# 06_Power.net
KiCad netlist of a schematic drawn in Altium Designer
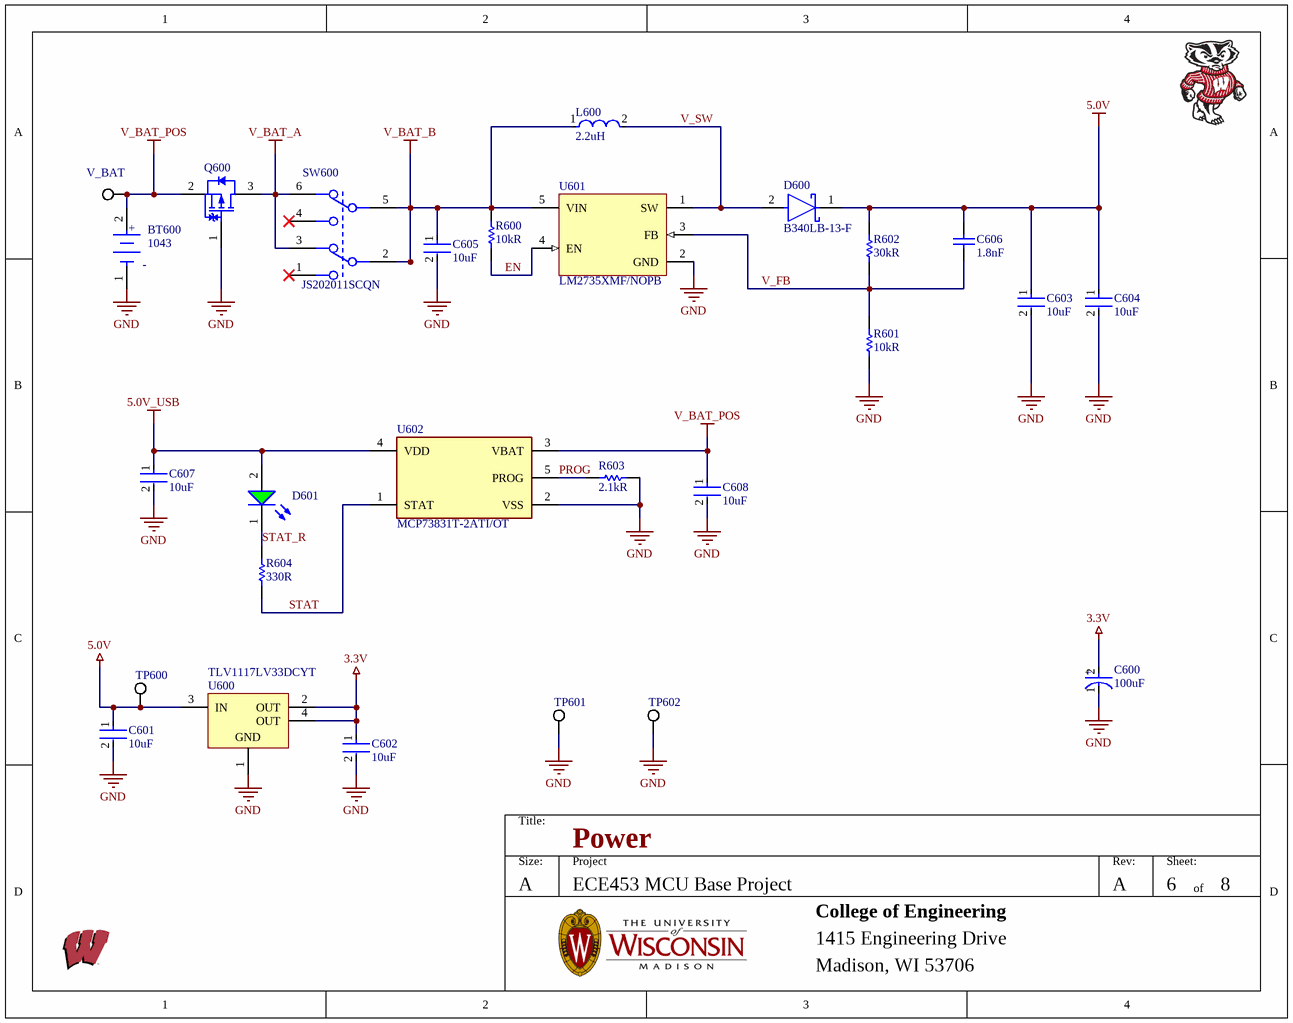
[diagram p0: 06_Power.SchDoc]

(export (version "E")
  (design (tool "Eeschema 10.0.6"))
  (components
    (comp (ref "BT600")
      (value "1043")
      (footprint "BAT_1043")
      (description "Conn Terminal Strip 2 POS Solder Lug ST")
      (fields
        (field (name "MANUFACTURER") "Keystone Electronics")
        (field (name "MANUFACTURER PART NUMBER 1") "1043")
      )
      (libsource (lib "ECE453_S24") (part "1043"))
    )
    (comp (ref "C600")
      (value "100uF")
      (footprint "FP-SD8-MFG")
      (description "CAP ALUM 100UF 20% 25V SMD")
      (fields (field (name "VOLTAGE") "25V") (field (name "TOLERANCE") "20%"))
      (libsource (lib "Altium Content Vault") (part "a00bbbee19879c290e62620ae7e47b1"))
    )
    (comp (ref "C601")
      (value "10uF")
      (footprint "FP-C0805C-DG-MFG")
      (description "CAP CER 10UF 10V X5R 0805")
      (fields (field (name "TOLERANCE") "10%") (field (name "MANUFACTURER PART NUMBER") "C0805C106K8PACTU"))
      (libsource (lib "Altium Content Vault") (part "11868f565c42a9108669ba33697ecf6"))
    )
    (comp (ref "C602")
      (value "10uF")
      (footprint "FP-C0805C-DG-MFG")
      (description "CAP CER 10UF 10V X5R 0805")
      (fields (field (name "TOLERANCE") "10%") (field (name "MANUFACTURER PART NUMBER") "C0805C106K8PACTU"))
      (libsource (lib "Altium Content Vault") (part "11868f565c42a9108669ba33697ecf6"))
    )
    (comp (ref "C603")
      (value "10uF")
      (footprint "FP-C0805C-DG-MFG")
      (description "CAP CER 10UF 10V X5R 0805")
      (fields (field (name "TOLERANCE") "10%") (field (name "MANUFACTURER PART NUMBER") "C0805C106K8PACTU"))
      (libsource (lib "Altium Content Vault") (part "11868f565c42a9108669ba33697ecf6"))
    )
    (comp (ref "C604")
      (value "10uF")
      (footprint "FP-C0805C-DG-MFG")
      (description "CAP CER 10UF 10V X5R 0805")
      (fields (field (name "TOLERANCE") "10%") (field (name "MANUFACTURER PART NUMBER") "C0805C106K8PACTU"))
      (libsource (lib "Altium Content Vault") (part "11868f565c42a9108669ba33697ecf6"))
    )
    (comp (ref "C605")
      (value "10uF")
      (footprint "FP-C0805C-DG-MFG")
      (description "CAP CER 10UF 10V X5R 0805")
      (fields (field (name "TOLERANCE") "10%") (field (name "MANUFACTURER PART NUMBER") "C0805C106K8PACTU"))
      (libsource (lib "Altium Content Vault") (part "11868f565c42a9108669ba33697ecf6"))
    )
    (comp (ref "C606")
      (value "1.8nF")
      (footprint "CAPC2013X70X45LL10T25")
      (fields (field (name "PART NUMBER") "GRM2165C1H182JA01D") (field (name "MANUFACTURER") "Murata"))
      (libsource (lib "Altium Content Vault") (part "CAP"))
    )
    (comp (ref "C607")
      (value "10uF")
      (footprint "FP-C0805C-DG-MFG")
      (description "CAP CER 10UF 10V X5R 0805")
      (fields (field (name "TOLERANCE") "10%") (field (name "MANUFACTURER PART NUMBER") "C0805C106K8PACTU"))
      (libsource (lib "Altium Content Vault") (part "11868f565c42a9108669ba33697ecf6"))
    )
    (comp (ref "C608")
      (value "10uF")
      (footprint "FP-C0805C-DG-MFG")
      (description "CAP CER 10UF 10V X5R 0805")
      (fields (field (name "TOLERANCE") "10%") (field (name "MANUFACTURER PART NUMBER") "C0805C106K8PACTU"))
      (libsource (lib "Altium Content Vault") (part "11868f565c42a9108669ba33697ecf6"))
    )
    (comp (ref "D600")
      (value "B340LB-13-F")
      (footprint "FP-SMB-MFG")
      (description "DIODE SCHOTTKY 40V 3A SMB")
      (fields
        (field (name "OCTOPART") "https://octopart.com/b340lb-13-f-diodes+inc.-325823")
        (field (name "MANUFACTURER") "Diodes Inc.")
      )
      (libsource (lib "Altium Content Vault") (part "1d6ec82d83fb6aee721767c19dac4b9"))
    )
    (comp (ref "D601")
      (value "~")
      (footprint "WL-SMCW_0805_150080xx75000")
      (libsource (lib "Altium Content Vault") (part "LED_Green_2A-1K"))
    )
    (comp (ref "L600")
      (value "2.2uH")
      (footprint "FP-NR4018-MFG")
      (description "SMD Power Inductors 2.2uH ±20% 2.2A 50.4mΩ")
      (fields (field (name "TOLERANCE") "20%"))
      (libsource (lib "Altium Content Vault") (part "725321dda6339637d4d059423bc1c3c"))
    )
    (comp (ref "Q600")
      (value "~")
      (footprint "TOSH-SOT-23F_V")
      (fields (field (name "MANUFACTURER") "Toshiba"))
      (libsource (lib "Altium Content Vault") (part "PEMOS-GSD-3_C"))
    )
    (comp (ref "R600")
      (value "10kR")
      (footprint "RESC2013X60X35NL10T20")
      (description "Chip Resistor, 10 KOhm, +/- 1%, 0.125 W, -55 to 155 degC, 0805 (2012 Metric), RoHS, Tape and Reel")
      (fields (field (name "MANUFACTURER") "Yageo"))
      (libsource (lib "Altium Content Vault") (part "RES-2"))
    )
    (comp (ref "R601")
      (value "10kR")
      (footprint "RESC2013X60X35NL10T20")
      (description "Chip Resistor, 10 KOhm, +/- 1%, 0.125 W, -55 to 155 degC, 0805 (2012 Metric), RoHS, Tape and Reel")
      (fields (field (name "MANUFACTURER") "Yageo"))
      (libsource (lib "Altium Content Vault") (part "RES-2"))
    )
    (comp (ref "R602")
      (value "30kR")
      (footprint "RESC2013X70X40LL20T20")
      (description "RES 30.0K OHM 1/8W 1% 0805 SMD")
      (fields (field (name "MANUFACTURER") "Panasonic") (field (name "PARTNUMBER") "ERJ-6ENF3002V"))
      (libsource (lib "") (part "RES-2_1"))
    )
    (comp (ref "R603")
      (value "2.1kR")
      (footprint "RESC2013X70X40ML20T20")
      (fields (field (name "PART NUMBER") "ERJ-6ENF2101V") (field (name "MANUFACTURER") "Panasonic"))
      (libsource (lib "Altium Content Vault") (part "RES"))
    )
    (comp (ref "R604")
      (value "330R")
      (footprint "RESC2013X60X40LL20T25")
      (fields (field (name "MANUFACTURER") "Panasonic") (field (name "PART NUMBER") "ERA6AEB331V"))
      (libsource (lib "Altium Content Vault") (part "RES"))
    )
    (comp (ref "SW600")
      (value "JS202011SCQN")
      (footprint "FP-JS202011SCQN-MFG")
      (description "SWITCH SLIDE DPDT 300MA 6V")
      (libsource (lib "Altium Content Vault") (part "ac99ea1af431c19115f5225061c5c88"))
    )
    (comp (ref "TP600")
      (value "~")
      (footprint "KSTN-5019_V")
      (description "Test Point, 1 Position SMD, RoHS, Tape and Reel")
      (libsource (lib "Altium Content Vault") (part "TESTPOINT_WHITE"))
    )
    (comp (ref "TP601")
      (value "~")
      (footprint "KSTN-5019_V")
      (description "Test Point, 1 Position SMD, RoHS, Tape and Reel")
      (libsource (lib "Altium Content Vault") (part "TESTPOINT_WHITE"))
    )
    (comp (ref "TP602")
      (value "~")
      (footprint "KSTN-5019_V")
      (description "Test Point, 1 Position SMD, RoHS, Tape and Reel")
      (libsource (lib "Altium Content Vault") (part "TESTPOINT_WHITE"))
    )
    (comp (ref "U600")
      (value "TLV1117LV33DCYT")
      (footprint "DCY0004A_M")
      (fields (field (name "MANUFACTURER") "Texas Instruments"))
      (libsource (lib "Altium Content Vault") (part "TI-TLV1117LV33DCY4"))
    )
    (comp (ref "U601")
      (value "LM2735XMF/NOPB")
      (footprint "DBV0005A_N")
      (description "520kHz/1.6MHz - Space-Efficient Boost and SEPIC DC-DC Regulator, 5-pin SOT-23, Pb-Free")
      (fields (field (name "MANUFACTURER") "Texas Instruments"))
      (libsource (lib "Altium Content Vault") (part "PM-DCDC-LM2735MF"))
    )
    (comp (ref "U602")
      (value "MCP73831T-2ATI/OT")
      (footprint "FP-C04-091-OT-IPC_C")
      (description "IC CONTROLLR LI-ION 4.2V SOT23-5")
      (libsource (lib "Altium Content Vault") (part "a15496f3f0dd9906c1bee5f8dba5d2c"))
    )
    (comp (ref "V_BAT")
      (value "~")
      (footprint "KSTN-5019_V")
      (description "Test Point, 1 Position SMD, RoHS, Tape and Reel")
      (libsource (lib "Altium Content Vault") (part "TESTPOINT_WHITE"))
    )
  )
  (nets
    (net (code "1") (name "/EN") (class "Default")
      (node (ref "R600") (pin "1") (pinfunction "1_1") (pintype "passive"))
      (node (ref "U601") (pin "4") (pinfunction "EN_4") (pintype "input"))
    )
    (net (code "2") (name "/PROG") (class "Default")
      (node (ref "R603") (pin "1") (pinfunction "1_1") (pintype "passive"))
      (node (ref "U602") (pin "5") (pinfunction "PROG_5") (pintype "passive"))
    )
    (net (code "3") (name "/STAT") (class "Default")
      (node (ref "R604") (pin "2") (pinfunction "2_2") (pintype "passive"))
      (node (ref "U602") (pin "1") (pinfunction "STAT_1") (pintype "passive"))
    )
    (net (code "4") (name "/STAT_R") (class "Default")
      (node (ref "D601") (pin "1") (pinfunction "K_1") (pintype "passive"))
      (node (ref "R604") (pin "1") (pinfunction "1_1") (pintype "passive"))
    )
    (net (code "5") (name "/V_FB") (class "Default")
      (node (ref "C606") (pin "1") (pinfunction "1_1") (pintype "passive"))
      (node (ref "R601") (pin "2") (pinfunction "2_2") (pintype "passive"))
      (node (ref "R602") (pin "1") (pinfunction "1_1") (pintype "passive"))
      (node (ref "U601") (pin "3") (pinfunction "FB_3") (pintype "input"))
    )
    (net (code "6") (name "/V_SW") (class "Default")
      (node (ref "D600") (pin "2") (pinfunction "A_2") (pintype "passive"))
      (node (ref "L600") (pin "2") (pinfunction "2_2") (pintype "passive"))
      (node (ref "U601") (pin "1") (pinfunction "SW_1") (pintype "power_in"))
    )
    (net (code "7") (name "3.3V") (class "Default")
      (node (ref "C600") (pin "2") (pinfunction "A_2") (pintype "passive"))
      (node (ref "C602") (pin "1") (pinfunction "1_1") (pintype "passive"))
      (node (ref "U600") (pin "2") (pinfunction "OUT_2") (pintype "power_in"))
      (node (ref "U600") (pin "4") (pinfunction "OUT_4") (pintype "power_in"))
    )
    (net (code "8") (name "5.0V") (class "Default")
      (node (ref "C601") (pin "1") (pinfunction "1_1") (pintype "passive"))
      (node (ref "C603") (pin "1") (pinfunction "1_1") (pintype "passive"))
      (node (ref "C604") (pin "1") (pinfunction "1_1") (pintype "passive"))
      (node (ref "C606") (pin "2") (pinfunction "2_2") (pintype "passive"))
      (node (ref "D600") (pin "1") (pinfunction "C_1") (pintype "passive"))
      (node (ref "R602") (pin "2") (pinfunction "2_2") (pintype "passive"))
      (node (ref "TP600") (pin "1") (pinfunction "1_1") (pintype "passive"))
      (node (ref "U600") (pin "3") (pinfunction "IN_3") (pintype "power_in"))
    )
    (net (code "9") (name "5.0V_USB") (class "Default")
      (node (ref "C607") (pin "1") (pinfunction "1_1") (pintype "passive"))
      (node (ref "D601") (pin "2") (pinfunction "A_2") (pintype "passive"))
      (node (ref "U602") (pin "4") (pinfunction "VDD_4") (pintype "power_in"))
    )
    (net (code "10") (name "GND") (class "Default")
      (node (ref "BT600") (pin "1") (pinfunction "C_1") (pintype "passive"))
      (node (ref "C600") (pin "1") (pinfunction "C_1") (pintype "passive"))
      (node (ref "C601") (pin "2") (pinfunction "2_2") (pintype "passive"))
      (node (ref "C602") (pin "2") (pinfunction "2_2") (pintype "passive"))
      (node (ref "C603") (pin "2") (pinfunction "2_2") (pintype "passive"))
      (node (ref "C604") (pin "2") (pinfunction "2_2") (pintype "passive"))
      (node (ref "C605") (pin "2") (pinfunction "2_2") (pintype "passive"))
      (node (ref "C607") (pin "2") (pinfunction "2_2") (pintype "passive"))
      (node (ref "C608") (pin "2") (pinfunction "2_2") (pintype "passive"))
      (node (ref "Q600") (pin "1") (pinfunction "G_1") (pintype "passive"))
      (node (ref "R601") (pin "1") (pinfunction "1_1") (pintype "passive"))
      (node (ref "R603") (pin "2") (pinfunction "2_2") (pintype "passive"))
      (node (ref "TP601") (pin "1") (pinfunction "1_1") (pintype "passive"))
      (node (ref "TP602") (pin "1") (pinfunction "1_1") (pintype "passive"))
      (node (ref "U600") (pin "1") (pinfunction "GND_1") (pintype "power_in"))
      (node (ref "U601") (pin "2") (pinfunction "GND_2") (pintype "power_in"))
      (node (ref "U602") (pin "2") (pinfunction "VSS_2") (pintype "power_in"))
    )
    (net (code "11") (name "V_BAT_A") (class "Default")
      (node (ref "Q600") (pin "3") (pinfunction "D_3") (pintype "passive"))
      (node (ref "SW600") (pin "3") (pinfunction "3_3") (pintype "passive"))
      (node (ref "SW600") (pin "6") (pinfunction "6_6") (pintype "passive"))
    )
    (net (code "12") (name "V_BAT_B") (class "Default")
      (node (ref "C605") (pin "1") (pinfunction "1_1") (pintype "passive"))
      (node (ref "L600") (pin "1") (pinfunction "1_1") (pintype "passive"))
      (node (ref "R600") (pin "2") (pinfunction "2_2") (pintype "passive"))
      (node (ref "SW600") (pin "2") (pinfunction "2_2") (pintype "passive"))
      (node (ref "SW600") (pin "5") (pinfunction "5_5") (pintype "passive"))
      (node (ref "U601") (pin "5") (pinfunction "VIN_5") (pintype "power_in"))
    )
    (net (code "13") (name "V_BAT_POS") (class "Default")
      (node (ref "BT600") (pin "2") (pinfunction "A_2") (pintype "passive"))
      (node (ref "C608") (pin "1") (pinfunction "1_1") (pintype "passive"))
      (node (ref "Q600") (pin "2") (pinfunction "S_2") (pintype "passive"))
      (node (ref "U602") (pin "3") (pinfunction "VBAT_3") (pintype "power_in"))
      (node (ref "V_BAT") (pin "1") (pinfunction "1_1") (pintype "passive"))
    )
    (net (code "14") (name "unconnected-(SW600-Pad1)") (class "Default")
      (node (ref "SW600") (pin "1") (pinfunction "1_1") (pintype "passive+no_connect"))
    )
    (net (code "15") (name "unconnected-(SW600-Pad4)") (class "Default")
      (node (ref "SW600") (pin "4") (pinfunction "4_4") (pintype "passive+no_connect"))
    )
  )
)
